# Blend_Control.net
KiCad netlist of a schematic drawn in EAGLE
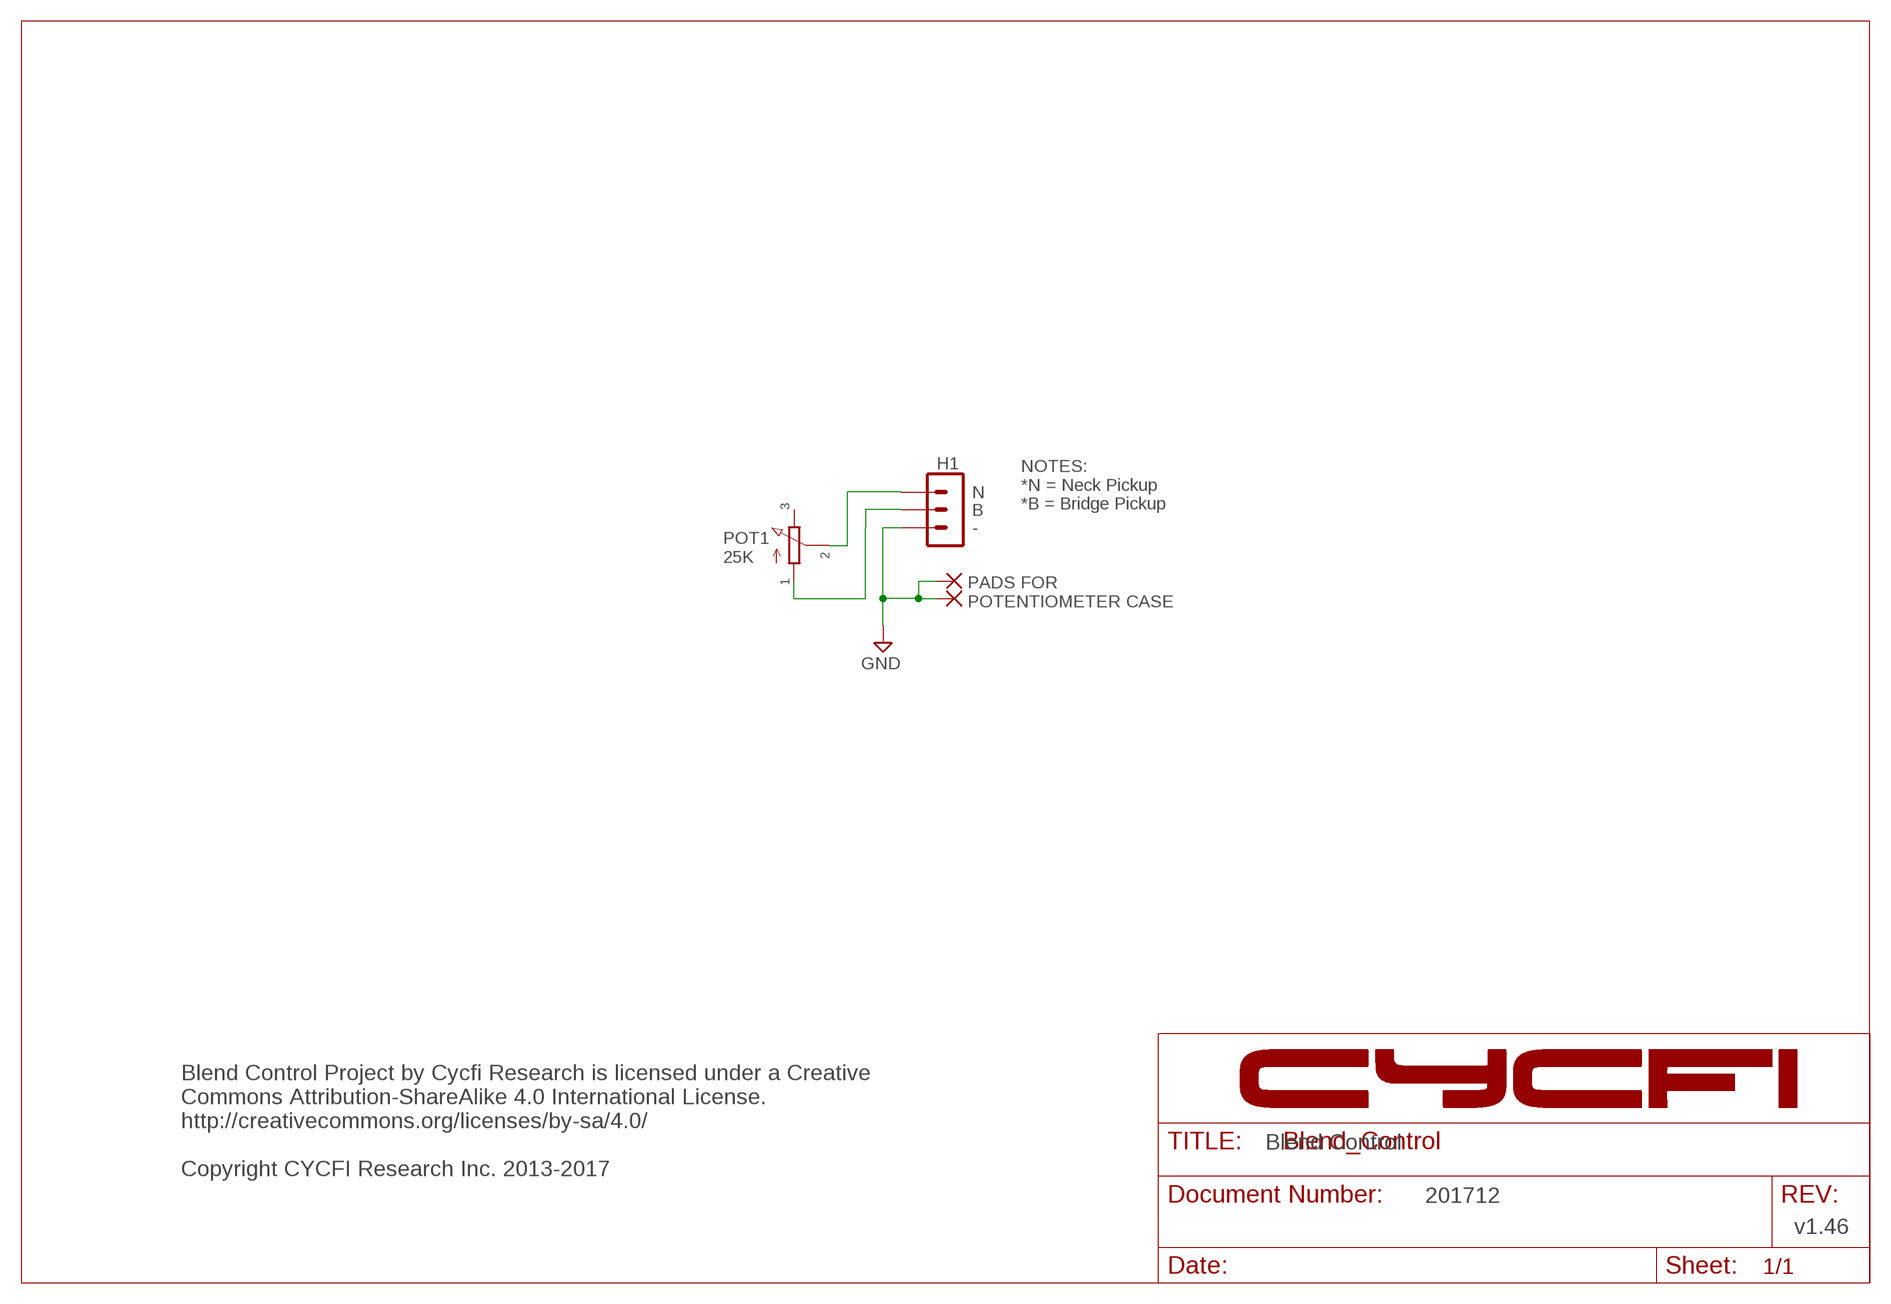
[diagram p0: schematic, sheet 1]

(export (version "E")
  (design (tool "Eeschema 10.0.6"))
  (components
    (comp (ref "GND3")
      (value "SMD2")
      (footprint "eagle-import:SMD1,27-2,54")
      (libsource (lib "eagle-import") (part "SMD2"))
    )
    (comp (ref "GND4")
      (value "SMD2")
      (footprint "eagle-import:SMD1,27-2,54")
      (libsource (lib "eagle-import") (part "SMD2"))
    )
    (comp (ref "H1")
      (value "3PIN-SMD-2.54MM")
      (footprint "eagle-import:3P-SMD-2.54MM")
      (libsource (lib "eagle-import") (part "3PIN-SMD-2.54MM"))
    )
    (comp (ref "POT1")
      (value "PDB181-GTR01")
      (footprint "eagle-import:PDB181")
      (libsource (lib "eagle-import") (part "PDB181-GTR01"))
    )
  )
  (nets
    (net (code "1") (name "GND") (class "Default")
      (node (ref "GND3") (pin "1") (pinfunction "P_1") (pintype "passive"))
      (node (ref "GND4") (pin "1") (pinfunction "P_1") (pintype "passive"))
      (node (ref "H1") (pin "P$1") (pinfunction "1_P$1") (pintype "passive"))
    )
    (net (code "2") (name "Net-(H1-2)") (class "Default")
      (node (ref "H1") (pin "P$2") (pinfunction "2_P$2") (pintype "passive"))
      (node (ref "POT1") (pin "P$1") (pinfunction "1_P$1") (pintype "passive"))
    )
    (net (code "3") (name "Net-(H1-3)") (class "Default")
      (node (ref "H1") (pin "P$3") (pinfunction "3_P$3") (pintype "passive"))
      (node (ref "POT1") (pin "P$2") (pinfunction "2_P$2") (pintype "passive"))
    )
    (net (code "4") (name "unconnected-(POT1-3-PadP$3)") (class "Default")
      (node (ref "POT1") (pin "P$3") (pinfunction "3_P$3") (pintype "passive"))
    )
  )
)
